# Opto-coupler_SMD-OM.net
KiCad netlist of a schematic drawn in EAGLE
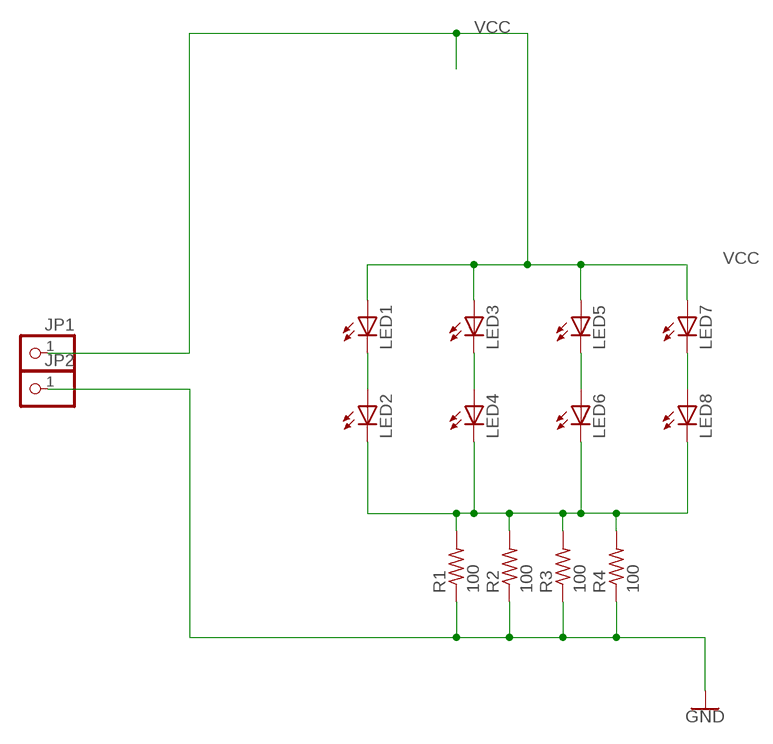
[diagram p0: schematic, sheet 1]

(export (version "E")
  (design (tool "Eeschema 10.0.6"))
  (components
    (comp (ref "JP1")
      (value "PINHD-1X1")
      (footprint "eagle-import:1X01")
      (libsource (lib "eagle-import") (part "PINHD-1X1"))
    )
    (comp (ref "JP2")
      (value "PINHD-1X1")
      (footprint "eagle-import:1X01")
      (libsource (lib "eagle-import") (part "PINHD-1X1"))
    )
    (comp (ref "LED1")
      (value "LEDCHIPLED_0603")
      (footprint "eagle-import:CHIPLED_0603")
      (libsource (lib "eagle-import") (part "LEDCHIPLED_0603"))
    )
    (comp (ref "LED2")
      (value "LEDCHIPLED_0603")
      (footprint "eagle-import:CHIPLED_0603")
      (libsource (lib "eagle-import") (part "LEDCHIPLED_0603"))
    )
    (comp (ref "LED3")
      (value "LEDCHIPLED_0603")
      (footprint "eagle-import:CHIPLED_0603")
      (libsource (lib "eagle-import") (part "LEDCHIPLED_0603"))
    )
    (comp (ref "LED4")
      (value "LEDCHIPLED_0603")
      (footprint "eagle-import:CHIPLED_0603")
      (libsource (lib "eagle-import") (part "LEDCHIPLED_0603"))
    )
    (comp (ref "LED5")
      (value "LEDCHIPLED_0603")
      (footprint "eagle-import:CHIPLED_0603")
      (libsource (lib "eagle-import") (part "LEDCHIPLED_0603"))
    )
    (comp (ref "LED6")
      (value "LEDCHIPLED_0603")
      (footprint "eagle-import:CHIPLED_0603")
      (libsource (lib "eagle-import") (part "LEDCHIPLED_0603"))
    )
    (comp (ref "LED7")
      (value "LEDCHIPLED_0603")
      (footprint "eagle-import:CHIPLED_0603")
      (libsource (lib "eagle-import") (part "LEDCHIPLED_0603"))
    )
    (comp (ref "LED8")
      (value "LEDCHIPLED_0603")
      (footprint "eagle-import:CHIPLED_0603")
      (libsource (lib "eagle-import") (part "LEDCHIPLED_0603"))
    )
    (comp (ref "R1")
      (value "100")
      (footprint "eagle-import:R0603")
      (libsource (lib "eagle-import") (part "R-US_R0603"))
    )
    (comp (ref "R2")
      (value "100")
      (footprint "eagle-import:R0603")
      (libsource (lib "eagle-import") (part "R-US_R0603"))
    )
    (comp (ref "R3")
      (value "100")
      (footprint "eagle-import:R0603")
      (libsource (lib "eagle-import") (part "R-US_R0603"))
    )
    (comp (ref "R4")
      (value "100")
      (footprint "eagle-import:R0603")
      (libsource (lib "eagle-import") (part "R-US_R0603"))
    )
  )
  (nets
    (net (code "1") (name "/VCC") (class "Default")
      (node (ref "JP1") (pin "1") (pinfunction "1_1") (pintype "passive"))
      (node (ref "LED1") (pin "A") (pinfunction "A_A") (pintype "passive"))
      (node (ref "LED3") (pin "A") (pinfunction "A_A") (pintype "passive"))
      (node (ref "LED5") (pin "A") (pinfunction "A_A") (pintype "passive"))
      (node (ref "LED7") (pin "A") (pinfunction "A_A") (pintype "passive"))
    )
    (net (code "2") (name "GND") (class "Default")
      (node (ref "JP2") (pin "1") (pinfunction "1_1") (pintype "passive"))
      (node (ref "R1") (pin "1") (pinfunction "1_1") (pintype "passive"))
      (node (ref "R2") (pin "1") (pinfunction "1_1") (pintype "passive"))
      (node (ref "R3") (pin "1") (pinfunction "1_1") (pintype "passive"))
      (node (ref "R4") (pin "1") (pinfunction "1_1") (pintype "passive"))
    )
    (net (code "3") (name "Net-(LED1-PadC)") (class "Default")
      (node (ref "LED1") (pin "C") (pinfunction "C_C") (pintype "passive"))
      (node (ref "LED2") (pin "A") (pinfunction "A_A") (pintype "passive"))
    )
    (net (code "4") (name "Net-(LED2-PadC)") (class "Default")
      (node (ref "LED2") (pin "C") (pinfunction "C_C") (pintype "passive"))
      (node (ref "LED4") (pin "C") (pinfunction "C_C") (pintype "passive"))
      (node (ref "LED6") (pin "C") (pinfunction "C_C") (pintype "passive"))
      (node (ref "LED8") (pin "C") (pinfunction "C_C") (pintype "passive"))
      (node (ref "R1") (pin "2") (pinfunction "2_2") (pintype "passive"))
      (node (ref "R2") (pin "2") (pinfunction "2_2") (pintype "passive"))
      (node (ref "R3") (pin "2") (pinfunction "2_2") (pintype "passive"))
      (node (ref "R4") (pin "2") (pinfunction "2_2") (pintype "passive"))
    )
    (net (code "5") (name "Net-(LED3-PadC)") (class "Default")
      (node (ref "LED3") (pin "C") (pinfunction "C_C") (pintype "passive"))
      (node (ref "LED4") (pin "A") (pinfunction "A_A") (pintype "passive"))
    )
    (net (code "6") (name "Net-(LED5-PadC)") (class "Default")
      (node (ref "LED5") (pin "C") (pinfunction "C_C") (pintype "passive"))
      (node (ref "LED6") (pin "A") (pinfunction "A_A") (pintype "passive"))
    )
    (net (code "7") (name "Net-(LED7-PadC)") (class "Default")
      (node (ref "LED7") (pin "C") (pinfunction "C_C") (pintype "passive"))
      (node (ref "LED8") (pin "A") (pinfunction "A_A") (pintype "passive"))
    )
  )
)
